# connectors-extension.net
KiCad netlist of a schematic drawn in Altium Designer
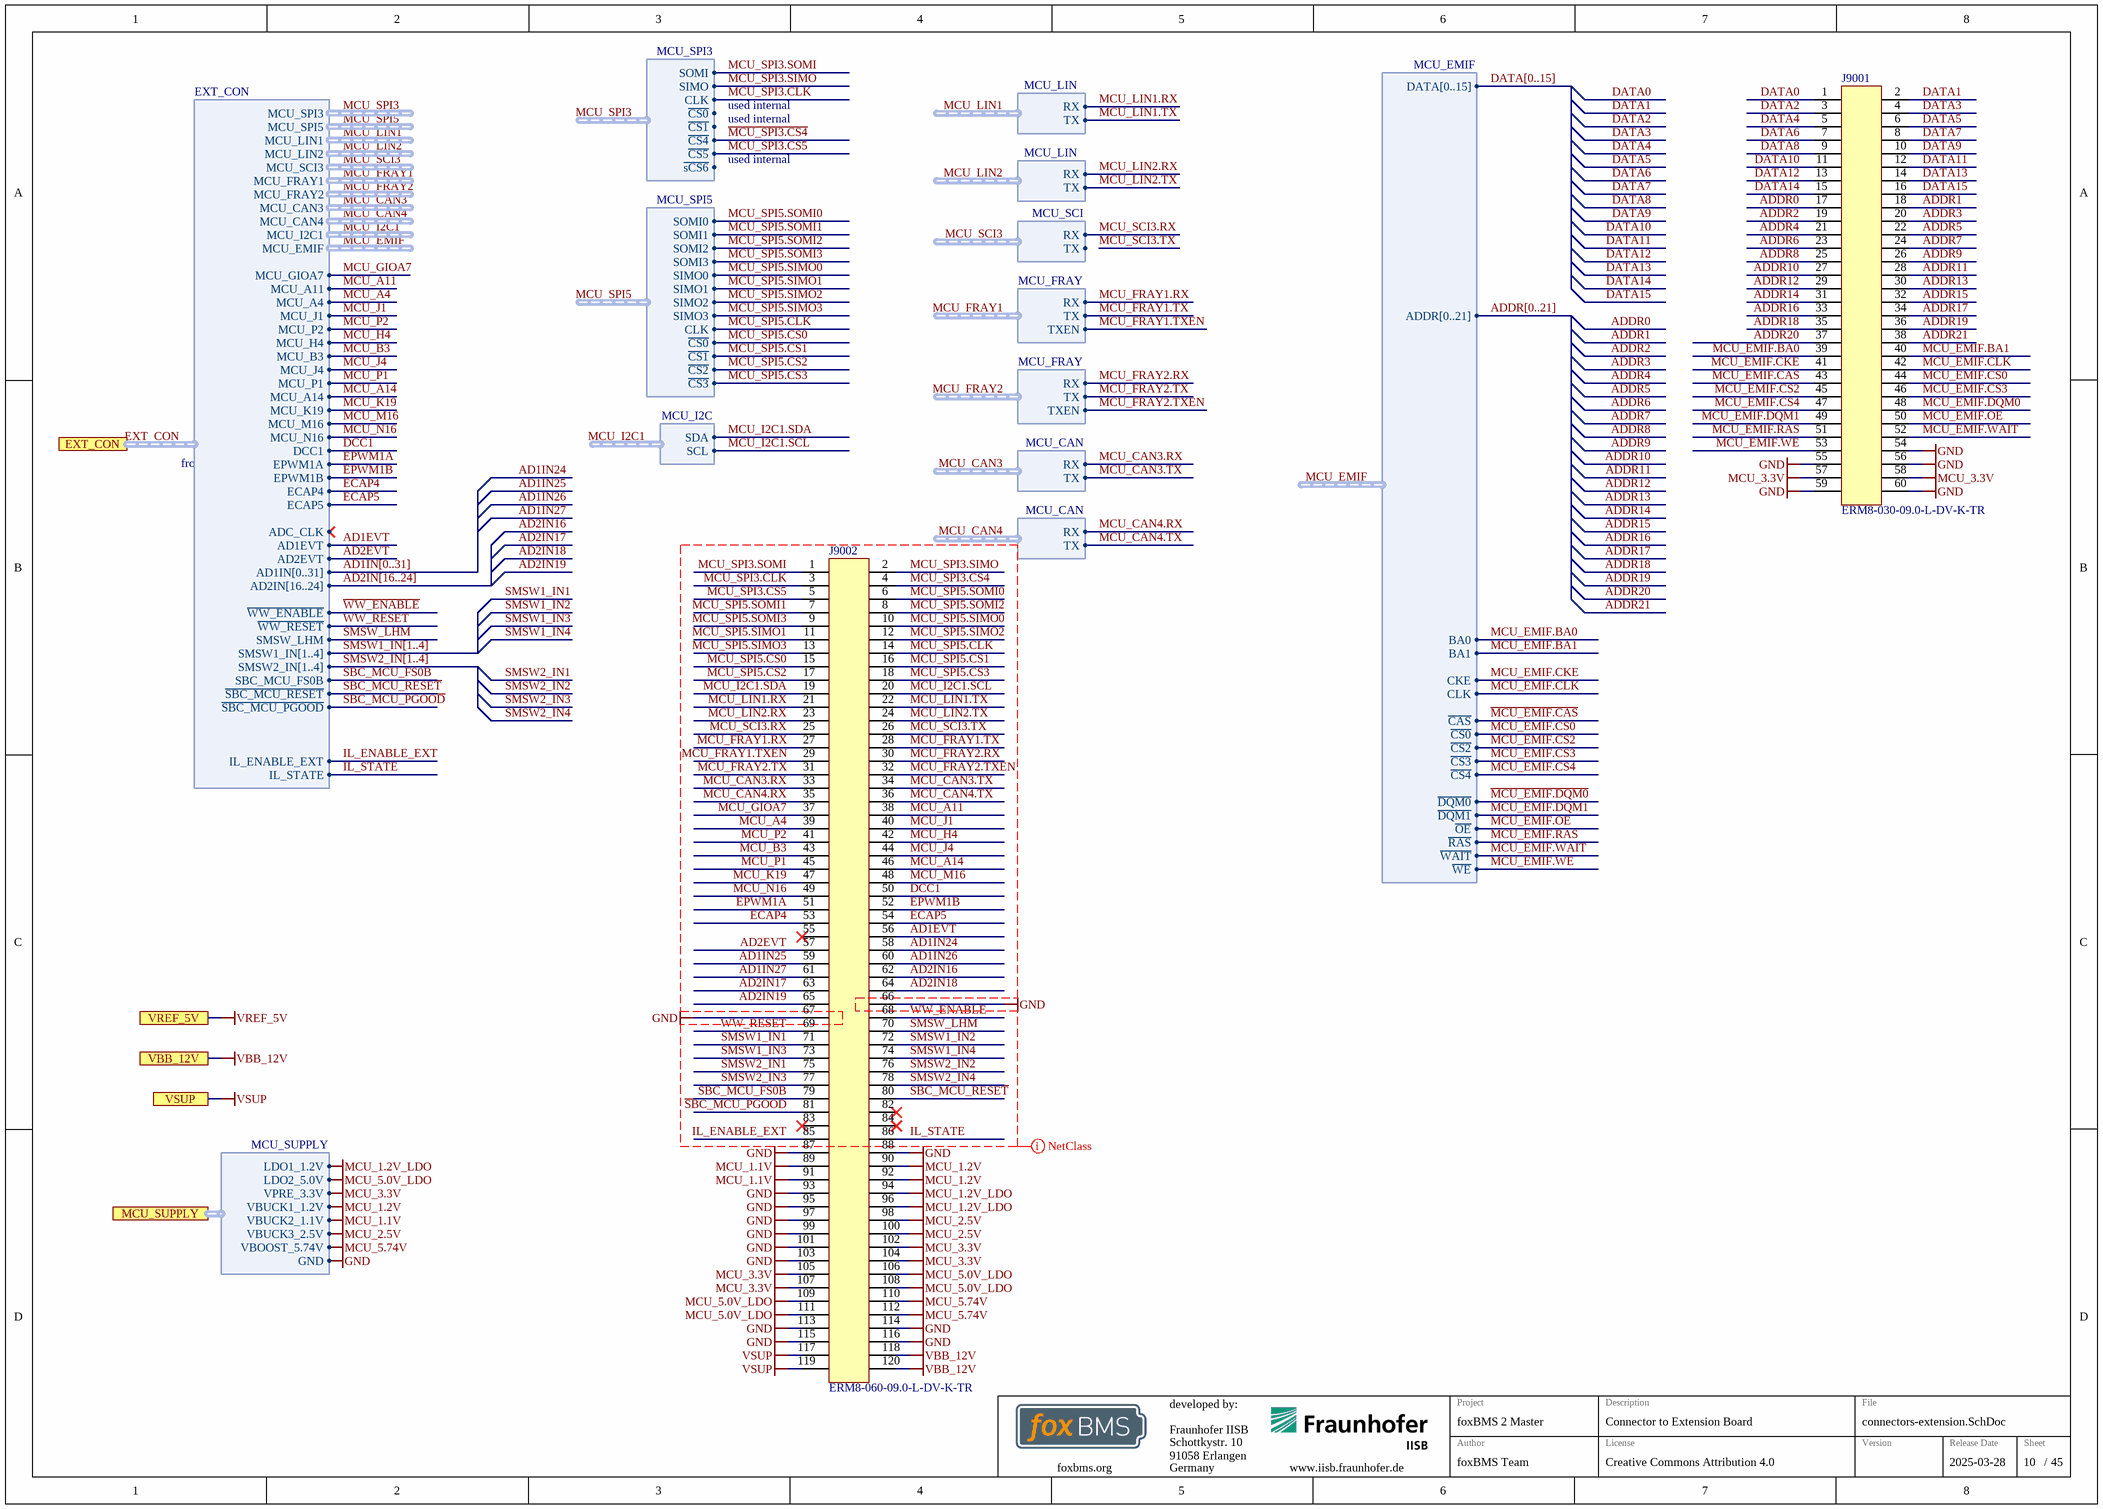
[diagram p0: connectors-extension.SchDoc]

(export (version "E")
  (design (tool "Eeschema 10.0.6"))
  (components
    (comp (ref "J9001")
      (value "ERM8-030-09.0-L-DV-K-TR")
      (footprint "SAMTEC_ERM8-030-09.0-L-DV-K")
      (description "Edge Rate rugged high-speed connector strips")
      (fields
        (field (name "PART NUMBER") "SAMTEC_ERM8-030-09.0-L-DV-K-TR")
        (field (name "MANUFACTURER") "Samtec")
      )
      (libsource (lib "OE750") (part "SAMTEC_ERM8-030-09.0-L-DV-K"))
    )
    (comp (ref "J9002")
      (value "ERM8-060-09.0-L-DV-K-TR")
      (footprint "SAMTEC_ERM8-060-09.0-L-DV-K")
      (description "Edge Rate rugged high-speed connector strips")
      (fields
        (field (name "PART NUMBER") "SAMTEC_ERM8-060-09.0-L-DV-K-TR")
        (field (name "MANUFACTURER") "Samtec")
      )
      (libsource (lib "OE750") (part "SAMTEC_ERM8-060-09.0-L-DV-K"))
    )
  )
  (nets
    (net (code "58") (name "/AD1EVT") (class "Default") (node (ref "J9002") (pin "56") (pintype "passive")))
    (net (code "59") (name "/AD1IN24") (class "Default") (node (ref "J9002") (pin "58") (pintype "passive")))
    (net (code "60") (name "/AD1IN25") (class "Default") (node (ref "J9002") (pin "59") (pintype "passive")))
    (net (code "61") (name "/AD1IN26") (class "Default") (node (ref "J9002") (pin "60") (pintype "passive")))
    (net (code "62") (name "/AD1IN27") (class "Default") (node (ref "J9002") (pin "61") (pintype "passive")))
    (net (code "64") (name "/AD2EVT") (class "Default") (node (ref "J9002") (pin "57") (pintype "passive")))
    (net (code "65") (name "/AD2IN16") (class "Default") (node (ref "J9002") (pin "62") (pintype "passive")))
    (net (code "66") (name "/AD2IN17") (class "Default") (node (ref "J9002") (pin "63") (pintype "passive")))
    (net (code "67") (name "/AD2IN18") (class "Default") (node (ref "J9002") (pin "64") (pintype "passive")))
    (net (code "68") (name "/AD2IN19") (class "Default") (node (ref "J9002") (pin "65") (pintype "passive")))
    (net (code "70") (name "/ADDR0") (class "Default") (node (ref "J9001") (pin "17") (pintype "passive")))
    (net (code "71") (name "/ADDR1") (class "Default") (node (ref "J9001") (pin "18") (pintype "passive")))
    (net (code "72") (name "/ADDR2") (class "Default") (node (ref "J9001") (pin "19") (pintype "passive")))
    (net (code "73") (name "/ADDR3") (class "Default") (node (ref "J9001") (pin "20") (pintype "passive")))
    (net (code "74") (name "/ADDR4") (class "Default") (node (ref "J9001") (pin "21") (pintype "passive")))
    (net (code "75") (name "/ADDR5") (class "Default") (node (ref "J9001") (pin "22") (pintype "passive")))
    (net (code "76") (name "/ADDR6") (class "Default") (node (ref "J9001") (pin "23") (pintype "passive")))
    (net (code "77") (name "/ADDR7") (class "Default") (node (ref "J9001") (pin "24") (pintype "passive")))
    (net (code "78") (name "/ADDR8") (class "Default") (node (ref "J9001") (pin "25") (pintype "passive")))
    (net (code "79") (name "/ADDR9") (class "Default") (node (ref "J9001") (pin "26") (pintype "passive")))
    (net (code "80") (name "/ADDR10") (class "Default") (node (ref "J9001") (pin "27") (pintype "passive")))
    (net (code "81") (name "/ADDR11") (class "Default") (node (ref "J9001") (pin "28") (pintype "passive")))
    (net (code "82") (name "/ADDR12") (class "Default") (node (ref "J9001") (pin "29") (pintype "passive")))
    (net (code "83") (name "/ADDR13") (class "Default") (node (ref "J9001") (pin "30") (pintype "passive")))
    (net (code "84") (name "/ADDR14") (class "Default") (node (ref "J9001") (pin "31") (pintype "passive")))
    (net (code "85") (name "/ADDR15") (class "Default") (node (ref "J9001") (pin "32") (pintype "passive")))
    (net (code "86") (name "/ADDR16") (class "Default") (node (ref "J9001") (pin "33") (pintype "passive")))
    (net (code "87") (name "/ADDR17") (class "Default") (node (ref "J9001") (pin "34") (pintype "passive")))
    (net (code "88") (name "/ADDR18") (class "Default") (node (ref "J9001") (pin "35") (pintype "passive")))
    (net (code "89") (name "/ADDR19") (class "Default") (node (ref "J9001") (pin "36") (pintype "passive")))
    (net (code "90") (name "/ADDR20") (class "Default") (node (ref "J9001") (pin "37") (pintype "passive")))
    (net (code "91") (name "/ADDR21") (class "Default") (node (ref "J9001") (pin "38") (pintype "passive")))
    (net (code "93") (name "/DATA0") (class "Default") (node (ref "J9001") (pin "1") (pintype "passive")))
    (net (code "94") (name "/DATA1") (class "Default") (node (ref "J9001") (pin "2") (pintype "passive")))
    (net (code "95") (name "/DATA2") (class "Default") (node (ref "J9001") (pin "3") (pintype "passive")))
    (net (code "96") (name "/DATA3") (class "Default") (node (ref "J9001") (pin "4") (pintype "passive")))
    (net (code "97") (name "/DATA4") (class "Default") (node (ref "J9001") (pin "5") (pintype "passive")))
    (net (code "98") (name "/DATA5") (class "Default") (node (ref "J9001") (pin "6") (pintype "passive")))
    (net (code "99") (name "/DATA6") (class "Default") (node (ref "J9001") (pin "7") (pintype "passive")))
    (net (code "100") (name "/DATA7") (class "Default") (node (ref "J9001") (pin "8") (pintype "passive")))
    (net (code "101") (name "/DATA8") (class "Default") (node (ref "J9001") (pin "9") (pintype "passive")))
    (net (code "102") (name "/DATA9") (class "Default") (node (ref "J9001") (pin "10") (pintype "passive")))
    (net (code "103") (name "/DATA10") (class "Default") (node (ref "J9001") (pin "11") (pintype "passive")))
    (net (code "104") (name "/DATA11") (class "Default") (node (ref "J9001") (pin "12") (pintype "passive")))
    (net (code "105") (name "/DATA12") (class "Default") (node (ref "J9001") (pin "13") (pintype "passive")))
    (net (code "106") (name "/DATA13") (class "Default") (node (ref "J9001") (pin "14") (pintype "passive")))
    (net (code "107") (name "/DATA14") (class "Default") (node (ref "J9001") (pin "15") (pintype "passive")))
    (net (code "108") (name "/DATA15") (class "Default") (node (ref "J9001") (pin "16") (pintype "passive")))
    (net (code "110") (name "/DCC1") (class "Default") (node (ref "J9002") (pin "50") (pintype "passive")))
    (net (code "111") (name "/ECAP4") (class "Default") (node (ref "J9002") (pin "53") (pintype "passive")))
    (net (code "112") (name "/ECAP5") (class "Default") (node (ref "J9002") (pin "54") (pintype "passive")))
    (net (code "113") (name "/EPWM1A") (class "Default") (node (ref "J9002") (pin "51") (pintype "passive")))
    (net (code "114") (name "/EPWM1B") (class "Default") (node (ref "J9002") (pin "52") (pintype "passive")))
    (net (code "115") (name "/IL_ENABLE_EXT") (class "Default")
      (node (ref "J9002") (pin "85") (pintype "passive"))
    )
    (net (code "116") (name "/IL_STATE") (class "Default")
      (node (ref "J9002") (pin "86") (pintype "passive"))
    )
    (net (code "117") (name "/MCU_A4") (class "Default") (node (ref "J9002") (pin "39") (pintype "passive")))
    (net (code "118") (name "/MCU_A11") (class "Default") (node (ref "J9002") (pin "38") (pintype "passive")))
    (net (code "119") (name "/MCU_A14") (class "Default") (node (ref "J9002") (pin "46") (pintype "passive")))
    (net (code "120") (name "/MCU_B3") (class "Default") (node (ref "J9002") (pin "43") (pintype "passive")))
    (net (code "121") (name "/MCU_CAN3.RX") (class "Default")
      (node (ref "J9002") (pin "33") (pintype "passive"))
    )
    (net (code "122") (name "/MCU_CAN3.TX") (class "Default")
      (node (ref "J9002") (pin "34") (pintype "passive"))
    )
    (net (code "124") (name "/MCU_CAN4.RX") (class "Default")
      (node (ref "J9002") (pin "35") (pintype "passive"))
    )
    (net (code "125") (name "/MCU_CAN4.TX") (class "Default")
      (node (ref "J9002") (pin "36") (pintype "passive"))
    )
    (net (code "127") (name "/MCU_EMIF.BA0") (class "Default")
      (node (ref "J9001") (pin "39") (pintype "passive"))
    )
    (net (code "128") (name "/MCU_EMIF.BA1") (class "Default")
      (node (ref "J9001") (pin "40") (pintype "passive"))
    )
    (net (code "129") (name "/MCU_EMIF.CAS") (class "Default")
      (node (ref "J9001") (pin "43") (pintype "passive"))
    )
    (net (code "130") (name "/MCU_EMIF.CKE") (class "Default")
      (node (ref "J9001") (pin "41") (pintype "passive"))
    )
    (net (code "131") (name "/MCU_EMIF.CLK") (class "Default")
      (node (ref "J9001") (pin "42") (pintype "passive"))
    )
    (net (code "132") (name "/MCU_EMIF.CS0") (class "Default")
      (node (ref "J9001") (pin "44") (pintype "passive"))
    )
    (net (code "133") (name "/MCU_EMIF.CS2") (class "Default")
      (node (ref "J9001") (pin "45") (pintype "passive"))
    )
    (net (code "134") (name "/MCU_EMIF.CS3") (class "Default")
      (node (ref "J9001") (pin "46") (pintype "passive"))
    )
    (net (code "135") (name "/MCU_EMIF.CS4") (class "Default")
      (node (ref "J9001") (pin "47") (pintype "passive"))
    )
    (net (code "136") (name "/MCU_EMIF.DQM0") (class "Default")
      (node (ref "J9001") (pin "48") (pintype "passive"))
    )
    (net (code "137") (name "/MCU_EMIF.DQM1") (class "Default")
      (node (ref "J9001") (pin "49") (pintype "passive"))
    )
    (net (code "138") (name "/MCU_EMIF.OE") (class "Default")
      (node (ref "J9001") (pin "50") (pintype "passive"))
    )
    (net (code "139") (name "/MCU_EMIF.RAS") (class "Default")
      (node (ref "J9001") (pin "51") (pintype "passive"))
    )
    (net (code "140") (name "/MCU_EMIF.WAIT") (class "Default")
      (node (ref "J9001") (pin "52") (pintype "passive"))
    )
    (net (code "141") (name "/MCU_EMIF.WE") (class "Default")
      (node (ref "J9001") (pin "53") (pintype "passive"))
    )
    (net (code "143") (name "/MCU_FRAY1.RX") (class "Default")
      (node (ref "J9002") (pin "27") (pintype "passive"))
    )
    (net (code "144") (name "/MCU_FRAY1.TX") (class "Default")
      (node (ref "J9002") (pin "28") (pintype "passive"))
    )
    (net (code "145") (name "/MCU_FRAY1.TXEN") (class "Default")
      (node (ref "J9002") (pin "29") (pintype "passive"))
    )
    (net (code "147") (name "/MCU_FRAY2.RX") (class "Default")
      (node (ref "J9002") (pin "30") (pintype "passive"))
    )
    (net (code "148") (name "/MCU_FRAY2.TX") (class "Default")
      (node (ref "J9002") (pin "31") (pintype "passive"))
    )
    (net (code "149") (name "/MCU_FRAY2.TXEN") (class "Default")
      (node (ref "J9002") (pin "32") (pintype "passive"))
    )
    (net (code "151") (name "/MCU_GIOA7") (class "Default")
      (node (ref "J9002") (pin "37") (pintype "passive"))
    )
    (net (code "152") (name "/MCU_H4") (class "Default") (node (ref "J9002") (pin "42") (pintype "passive")))
    (net (code "153") (name "/MCU_I2C1.SCL") (class "Default")
      (node (ref "J9002") (pin "20") (pintype "passive"))
    )
    (net (code "154") (name "/MCU_I2C1.SDA") (class "Default")
      (node (ref "J9002") (pin "19") (pintype "passive"))
    )
    (net (code "156") (name "/MCU_J1") (class "Default") (node (ref "J9002") (pin "40") (pintype "passive")))
    (net (code "157") (name "/MCU_J4") (class "Default") (node (ref "J9002") (pin "44") (pintype "passive")))
    (net (code "158") (name "/MCU_K19") (class "Default") (node (ref "J9002") (pin "47") (pintype "passive")))
    (net (code "159") (name "/MCU_LIN1.RX") (class "Default")
      (node (ref "J9002") (pin "21") (pintype "passive"))
    )
    (net (code "160") (name "/MCU_LIN1.TX") (class "Default")
      (node (ref "J9002") (pin "22") (pintype "passive"))
    )
    (net (code "162") (name "/MCU_LIN2.RX") (class "Default")
      (node (ref "J9002") (pin "23") (pintype "passive"))
    )
    (net (code "163") (name "/MCU_LIN2.TX") (class "Default")
      (node (ref "J9002") (pin "24") (pintype "passive"))
    )
    (net (code "165") (name "/MCU_M16") (class "Default") (node (ref "J9002") (pin "48") (pintype "passive")))
    (net (code "166") (name "/MCU_N16") (class "Default") (node (ref "J9002") (pin "49") (pintype "passive")))
    (net (code "167") (name "/MCU_P1") (class "Default") (node (ref "J9002") (pin "45") (pintype "passive")))
    (net (code "168") (name "/MCU_P2") (class "Default") (node (ref "J9002") (pin "41") (pintype "passive")))
    (net (code "169") (name "/MCU_SCI3.RX") (class "Default")
      (node (ref "J9002") (pin "25") (pintype "passive"))
    )
    (net (code "170") (name "/MCU_SCI3.TX") (class "Default")
      (node (ref "J9002") (pin "26") (pintype "passive"))
    )
    (net (code "172") (name "/MCU_SPI3.CLK") (class "Default")
      (node (ref "J9002") (pin "3") (pintype "passive"))
    )
    (net (code "173") (name "/MCU_SPI3.CS4") (class "Default")
      (node (ref "J9002") (pin "4") (pintype "passive"))
    )
    (net (code "174") (name "/MCU_SPI3.CS5") (class "Default")
      (node (ref "J9002") (pin "5") (pintype "passive"))
    )
    (net (code "175") (name "/MCU_SPI3.SIMO") (class "Default")
      (node (ref "J9002") (pin "2") (pintype "passive"))
    )
    (net (code "176") (name "/MCU_SPI3.SOMI") (class "Default")
      (node (ref "J9002") (pin "1") (pintype "passive"))
    )
    (net (code "179") (name "/MCU_SPI5.CLK") (class "Default")
      (node (ref "J9002") (pin "14") (pintype "passive"))
    )
    (net (code "180") (name "/MCU_SPI5.CS0") (class "Default")
      (node (ref "J9002") (pin "15") (pintype "passive"))
    )
    (net (code "181") (name "/MCU_SPI5.CS1") (class "Default")
      (node (ref "J9002") (pin "16") (pintype "passive"))
    )
    (net (code "182") (name "/MCU_SPI5.CS2") (class "Default")
      (node (ref "J9002") (pin "17") (pintype "passive"))
    )
    (net (code "183") (name "/MCU_SPI5.CS3") (class "Default")
      (node (ref "J9002") (pin "18") (pintype "passive"))
    )
    (net (code "184") (name "/MCU_SPI5.SIMO0") (class "Default")
      (node (ref "J9002") (pin "10") (pintype "passive"))
    )
    (net (code "185") (name "/MCU_SPI5.SIMO1") (class "Default")
      (node (ref "J9002") (pin "11") (pintype "passive"))
    )
    (net (code "186") (name "/MCU_SPI5.SIMO2") (class "Default")
      (node (ref "J9002") (pin "12") (pintype "passive"))
    )
    (net (code "187") (name "/MCU_SPI5.SIMO3") (class "Default")
      (node (ref "J9002") (pin "13") (pintype "passive"))
    )
    (net (code "188") (name "/MCU_SPI5.SOMI0") (class "Default")
      (node (ref "J9002") (pin "6") (pintype "passive"))
    )
    (net (code "189") (name "/MCU_SPI5.SOMI1") (class "Default")
      (node (ref "J9002") (pin "7") (pintype "passive"))
    )
    (net (code "190") (name "/MCU_SPI5.SOMI2") (class "Default")
      (node (ref "J9002") (pin "8") (pintype "passive"))
    )
    (net (code "191") (name "/MCU_SPI5.SOMI3") (class "Default")
      (node (ref "J9002") (pin "9") (pintype "passive"))
    )
    (net (code "193") (name "/SBC_MCU_FS0B") (class "Default")
      (node (ref "J9002") (pin "79") (pintype "passive"))
    )
    (net (code "194") (name "/SBC_MCU_PGOOD") (class "Default")
      (node (ref "J9002") (pin "81") (pintype "passive"))
    )
    (net (code "195") (name "/SBC_MCU_RESET") (class "Default")
      (node (ref "J9002") (pin "80") (pintype "passive"))
    )
    (net (code "196") (name "/SMSW1_IN1") (class "Default")
      (node (ref "J9002") (pin "71") (pintype "passive"))
    )
    (net (code "197") (name "/SMSW1_IN2") (class "Default")
      (node (ref "J9002") (pin "72") (pintype "passive"))
    )
    (net (code "198") (name "/SMSW1_IN3") (class "Default")
      (node (ref "J9002") (pin "73") (pintype "passive"))
    )
    (net (code "199") (name "/SMSW1_IN4") (class "Default")
      (node (ref "J9002") (pin "74") (pintype "passive"))
    )
    (net (code "201") (name "/SMSW2_IN1") (class "Default")
      (node (ref "J9002") (pin "75") (pintype "passive"))
    )
    (net (code "202") (name "/SMSW2_IN2") (class "Default")
      (node (ref "J9002") (pin "76") (pintype "passive"))
    )
    (net (code "203") (name "/SMSW2_IN3") (class "Default")
      (node (ref "J9002") (pin "77") (pintype "passive"))
    )
    (net (code "204") (name "/SMSW2_IN4") (class "Default")
      (node (ref "J9002") (pin "78") (pintype "passive"))
    )
    (net (code "206") (name "/SMSW_LHM") (class "Default")
      (node (ref "J9002") (pin "70") (pintype "passive"))
    )
    (net (code "207") (name "/WW_ENABLE") (class "Default")
      (node (ref "J9002") (pin "68") (pintype "passive"))
    )
    (net (code "208") (name "/WW_RESET") (class "Default")
      (node (ref "J9002") (pin "69") (pintype "passive"))
    )
    (net (code "221") (name "GND") (class "Default")
      (node (ref "J9001") (pin "54") (pintype "passive"))
      (node (ref "J9001") (pin "55") (pintype "passive"))
      (node (ref "J9001") (pin "56") (pintype "passive"))
      (node (ref "J9001") (pin "59") (pintype "passive"))
      (node (ref "J9001") (pin "60") (pintype "passive"))
      (node (ref "J9002") (pin "101") (pintype "passive"))
      (node (ref "J9002") (pin "103") (pintype "passive"))
      (node (ref "J9002") (pin "113") (pintype "passive"))
      (node (ref "J9002") (pin "114") (pintype "passive"))
      (node (ref "J9002") (pin "115") (pintype "passive"))
      (node (ref "J9002") (pin "116") (pintype "passive"))
      (node (ref "J9002") (pin "66") (pintype "passive"))
      (node (ref "J9002") (pin "67") (pintype "passive"))
      (node (ref "J9002") (pin "87") (pintype "passive"))
      (node (ref "J9002") (pin "88") (pintype "passive"))
      (node (ref "J9002") (pin "93") (pintype "passive"))
      (node (ref "J9002") (pin "95") (pintype "passive"))
      (node (ref "J9002") (pin "97") (pintype "passive"))
      (node (ref "J9002") (pin "99") (pintype "passive"))
    )
    (net (code "222") (name "MCU_1.1V") (class "Default")
      (node (ref "J9002") (pin "89") (pintype "passive"))
      (node (ref "J9002") (pin "91") (pintype "passive"))
    )
    (net (code "223") (name "MCU_1.2V") (class "Default")
      (node (ref "J9002") (pin "90") (pintype "passive"))
      (node (ref "J9002") (pin "92") (pintype "passive"))
    )
    (net (code "224") (name "MCU_1.2V_LDO") (class "Default")
      (node (ref "J9002") (pin "94") (pintype "passive"))
      (node (ref "J9002") (pin "96") (pintype "passive"))
    )
    (net (code "225") (name "MCU_2.5V") (class "Default")
      (node (ref "J9002") (pin "100") (pintype "passive"))
      (node (ref "J9002") (pin "98") (pintype "passive"))
    )
    (net (code "226") (name "MCU_3.3V") (class "Default")
      (node (ref "J9001") (pin "57") (pintype "passive"))
      (node (ref "J9001") (pin "58") (pintype "passive"))
      (node (ref "J9002") (pin "102") (pintype "passive"))
      (node (ref "J9002") (pin "104") (pintype "passive"))
      (node (ref "J9002") (pin "105") (pintype "passive"))
      (node (ref "J9002") (pin "107") (pintype "passive"))
    )
    (net (code "227") (name "MCU_5.0V_LDO") (class "Default")
      (node (ref "J9002") (pin "106") (pintype "passive"))
      (node (ref "J9002") (pin "108") (pintype "passive"))
      (node (ref "J9002") (pin "109") (pintype "passive"))
      (node (ref "J9002") (pin "111") (pintype "passive"))
    )
    (net (code "228") (name "MCU_5.74V") (class "Default")
      (node (ref "J9002") (pin "110") (pintype "passive"))
      (node (ref "J9002") (pin "112") (pintype "passive"))
    )
    (net (code "229") (name "VBB_12V") (class "Default")
      (node (ref "J9002") (pin "118") (pintype "passive"))
      (node (ref "J9002") (pin "120") (pintype "passive"))
    )
    (net (code "231") (name "VSUP") (class "Default")
      (node (ref "J9002") (pin "117") (pintype "passive"))
      (node (ref "J9002") (pin "119") (pintype "passive"))
    )
    (net (code "232") (name "unconnected-(J9002-Pad55)") (class "Default")
      (node (ref "J9002") (pin "55") (pintype "passive+no_connect"))
    )
    (net (code "233") (name "unconnected-(J9002-Pad82)") (class "Default")
      (node (ref "J9002") (pin "82") (pintype "passive+no_connect"))
    )
    (net (code "234") (name "unconnected-(J9002-Pad83)") (class "Default")
      (node (ref "J9002") (pin "83") (pintype "passive+no_connect"))
    )
    (net (code "235") (name "unconnected-(J9002-Pad84)") (class "Default")
      (node (ref "J9002") (pin "84") (pintype "passive+no_connect"))
    )
  )
)
